# ProProject_PetCareSTM32_MiniSTM32_2024-0.net
KiCad netlist of a schematic drawn in EasyEDA Pro
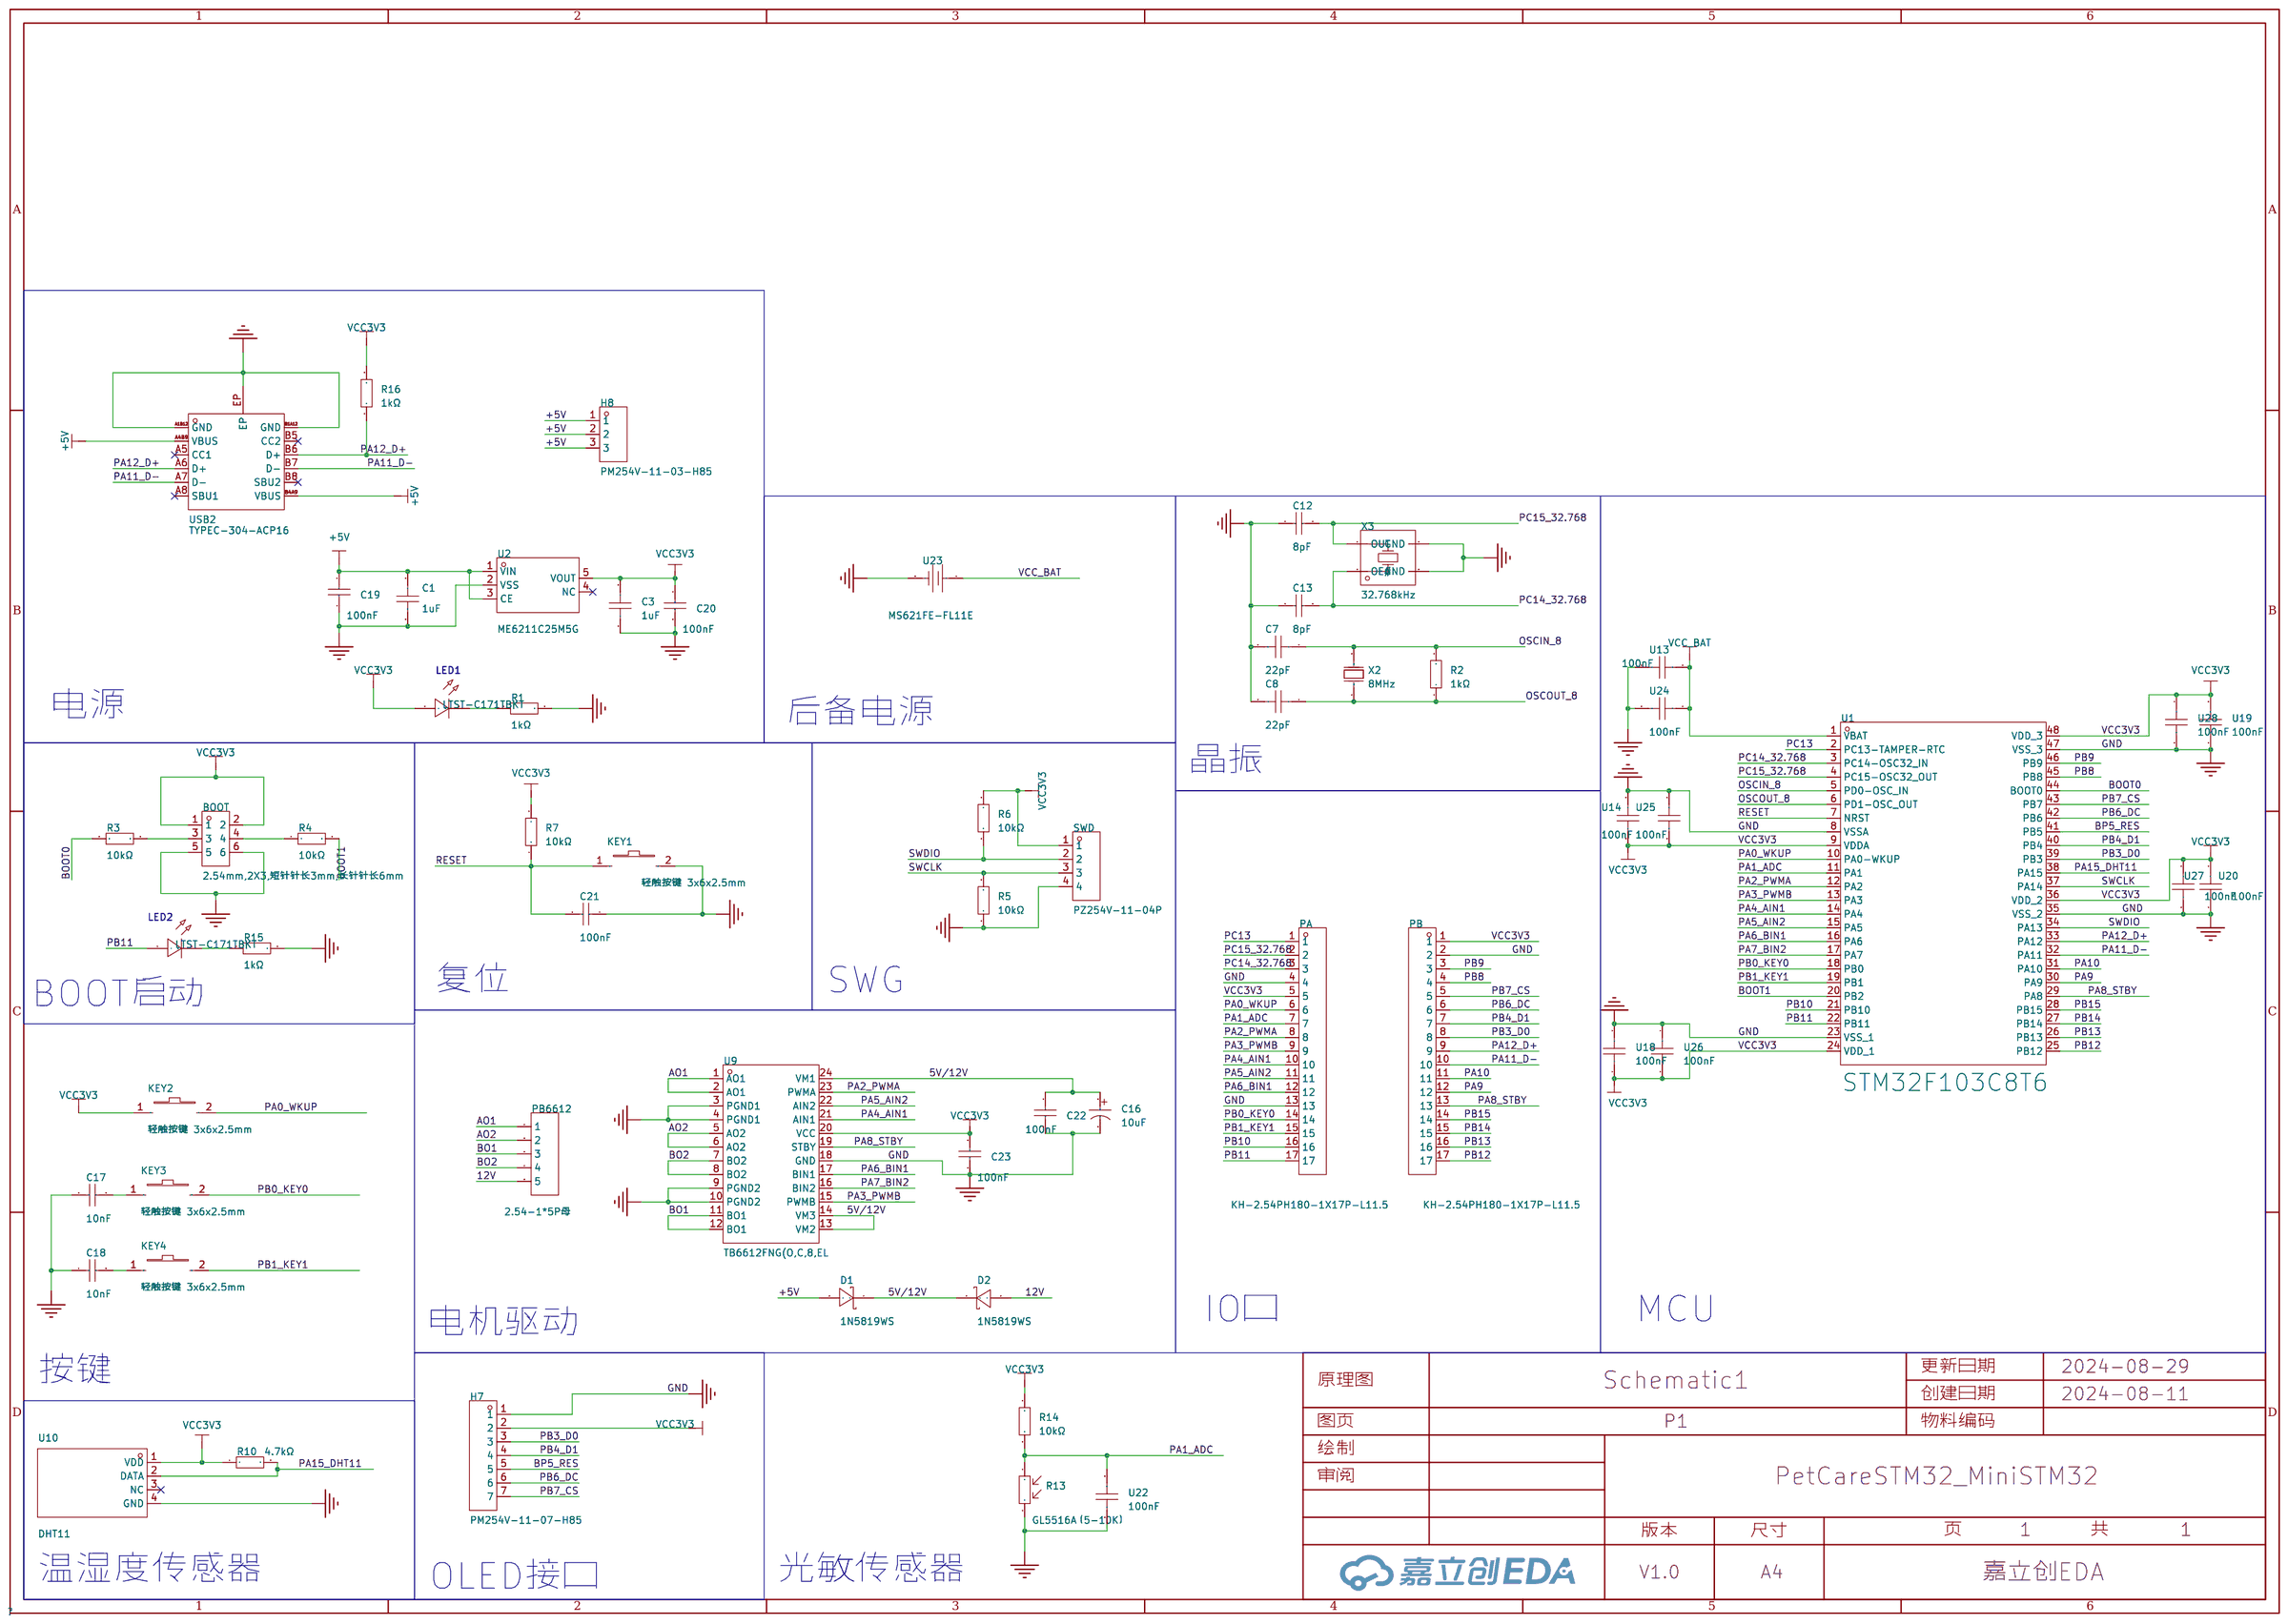
[diagram p0: schematic sheet]

(export (version "E")
  (design (tool "Eeschema 10.0.6"))
  (components
    (comp (ref "BOOT")
      (value "2.54mm,2X3,短针针长3mm,长针针长6mm")
      (footprint "easyedapro:HDR-TH_6P-P2.54-V-M-R2-C3-S2.54-2")
      (libsource (lib "easyedapro") (part "2.54MM,2X3,短针针长3MM,长针针长6MM"))
    )
    (comp (ref "C1")
      (value "1uF")
      (footprint "easyedapro:C0603")
      (description "容值:1uF;精度:±10%;额定电压:50V;材质(温度系数):X5R;")
      (fields
        (field (name "Manufacturer Part") "CL10A105KB8NNNC")
        (field (name "Manufacturer") "SAMSUNG(三星)")
      )
      (libsource (lib "easyedapro") (part "CL10A105KB8NNNC"))
    )
    (comp (ref "C3")
      (value "1uF")
      (footprint "easyedapro:C0603")
      (description "容值:1uF;精度:±10%;额定电压:50V;材质(温度系数):X5R;")
      (fields
        (field (name "Manufacturer Part") "CL10A105KB8NNNC")
        (field (name "Manufacturer") "SAMSUNG(三星)")
      )
      (libsource (lib "easyedapro") (part "CL10A105KB8NNNC"))
    )
    (comp (ref "C7")
      (value "22pF")
      (footprint "easyedapro:C0603")
      (description "容值:22pF;精度:±5%;额定电压:50V;材质(温度系数):C0G;")
      (fields
        (field (name "Manufacturer Part") "CL10C220JB81PNC")
        (field (name "Manufacturer") "SAMSUNG(三星)")
      )
      (libsource (lib "easyedapro") (part "CL10C220JB81PNC"))
    )
    (comp (ref "C8")
      (value "22pF")
      (footprint "easyedapro:C0603")
      (description "容值:22pF;精度:±5%;额定电压:50V;材质(温度系数):C0G;")
      (fields
        (field (name "Manufacturer Part") "CL10C220JB81PNC")
        (field (name "Manufacturer") "SAMSUNG(三星)")
      )
      (libsource (lib "easyedapro") (part "CL10C220JB81PNC"))
    )
    (comp (ref "C12")
      (value "8pF")
      (footprint "easyedapro:C0603")
      (description "容值:8pF;额定电压:50V;材质(温度系数):C0G;")
      (fields (field (name "Manufacturer Part") "0603CG8R0C500NT") (field (name "Manufacturer") "FH(风华)"))
      (libsource (lib "easyedapro") (part "0603CG8R0C500NT_C36508"))
    )
    (comp (ref "C13")
      (value "8pF")
      (footprint "easyedapro:C0603")
      (description "容值:8pF;额定电压:50V;材质(温度系数):C0G;")
      (fields (field (name "Manufacturer Part") "0603CG8R0C500NT") (field (name "Manufacturer") "FH(风华)"))
      (libsource (lib "easyedapro") (part "0603CG8R0C500NT_C36508"))
    )
    (comp (ref "C16")
      (value "10uF")
      (footprint "easyedapro:CAP-TH_BD5.0-P2.00-D0.8-FD")
      (description "容值:10uF;精度:±20%;额定电压:25V;")
      (fields (field (name "Manufacturer Part") "KF100M025C110A") (field (name "Manufacturer") "CapXon(丰宾)"))
      (libsource (lib "easyedapro") (part "KF100M025C110A"))
    )
    (comp (ref "C17")
      (value "10nF")
      (footprint "easyedapro:C0603")
      (description "容值:10nF;精度:±10%;额定电压:50V;材质(温度系数):X7R;")
      (fields
        (field (name "Manufacturer Part") "CC0603KRX7R9BB103")
        (field (name "Manufacturer") "YAGEO(国巨)")
      )
      (libsource (lib "easyedapro") (part "CC0603KRX7R9BB103"))
    )
    (comp (ref "C18")
      (value "10nF")
      (footprint "easyedapro:C0603")
      (description "容值:10nF;精度:±10%;额定电压:50V;材质(温度系数):X7R;")
      (fields
        (field (name "Manufacturer Part") "CC0603KRX7R9BB103")
        (field (name "Manufacturer") "YAGEO(国巨)")
      )
      (libsource (lib "easyedapro") (part "CC0603KRX7R9BB103"))
    )
    (comp (ref "C19")
      (value "100nF")
      (footprint "easyedapro:C0805")
      (description "容值:100nF;精度:±10%;额定电压:50V;材质(温度系数):X7R;")
      (fields
        (field (name "Manufacturer Part") "CL21B104KBCNNNC")
        (field (name "Manufacturer") "SAMSUNG(三星)")
      )
      (libsource (lib "easyedapro") (part "CL21B104KBCNNNC"))
    )
    (comp (ref "C20")
      (value "100nF")
      (footprint "easyedapro:C0805")
      (description "容值:100nF;精度:±10%;额定电压:50V;材质(温度系数):X7R;")
      (fields
        (field (name "Manufacturer Part") "CL21B104KBCNNNC")
        (field (name "Manufacturer") "SAMSUNG(三星)")
      )
      (libsource (lib "easyedapro") (part "CL21B104KBCNNNC"))
    )
    (comp (ref "C21")
      (value "100nF")
      (footprint "easyedapro:C0805")
      (description "容值:100nF;精度:±10%;额定电压:50V;材质(温度系数):X7R;")
      (fields
        (field (name "Manufacturer Part") "CL21B104KBCNNNC")
        (field (name "Manufacturer") "SAMSUNG(三星)")
      )
      (libsource (lib "easyedapro") (part "CL21B104KBCNNNC"))
    )
    (comp (ref "C22")
      (value "100nF")
      (footprint "easyedapro:C0805")
      (description "容值:100nF;精度:±10%;额定电压:50V;材质(温度系数):X7R;")
      (fields
        (field (name "Manufacturer Part") "CL21B104KBCNNNC")
        (field (name "Manufacturer") "SAMSUNG(三星)")
      )
      (libsource (lib "easyedapro") (part "CL21B104KBCNNNC"))
    )
    (comp (ref "C23")
      (value "100nF")
      (footprint "easyedapro:C0805")
      (description "容值:100nF;精度:±10%;额定电压:50V;材质(温度系数):X7R;")
      (fields
        (field (name "Manufacturer Part") "CL21B104KBCNNNC")
        (field (name "Manufacturer") "SAMSUNG(三星)")
      )
      (libsource (lib "easyedapro") (part "CL21B104KBCNNNC"))
    )
    (comp (ref "D1")
      (value "1N5819WS")
      (footprint "easyedapro:SOD-323_L1.8-W1.3-LS2.5-RD")
      (description "正向压降(Vf):600mV@1A;直流反向耐压(Vr):40V;平均整流电流(Io):1A;")
      (fields (field (name "Manufacturer") "Hottech(合科泰)"))
      (libsource (lib "easyedapro") (part "1N5819WS"))
    )
    (comp (ref "D2")
      (value "1N5819WS")
      (footprint "easyedapro:SOD-323_L1.8-W1.3-LS2.5-RD")
      (description "正向压降(Vf):600mV@1A;直流反向耐压(Vr):40V;平均整流电流(Io):1A;")
      (fields (field (name "Manufacturer") "Hottech(合科泰)"))
      (libsource (lib "easyedapro") (part "1N5819WS"))
    )
    (comp (ref "H7")
      (value "PM254V-11-07-H85")
      (footprint "easyedapro:HDR-TH_7P-P2.54-V-F")
      (fields (field (name "Manufacturer") "XFCN(兴飞)"))
      (libsource (lib "easyedapro") (part "PM254V-11-07-H85"))
    )
    (comp (ref "H8")
      (value "PM254V-11-03-H85")
      (footprint "easyedapro:HDR-TH_3P-P2.54-V-F")
      (description "插孔结构:1x3P;间距:2.54mm;行距:-;安装类型:直插;排数:单排;总孔位数:3P;塑高:-;触头材质:黄铜;触头镀层:-;")
      (fields (field (name "Manufacturer") "XFCN(兴飞)"))
      (libsource (lib "easyedapro") (part "PM254V-11-03-H85"))
    )
    (comp (ref "KEY1")
      (value "轻触按键 3x6x2.5mm")
      (footprint "easyedapro:SW-SMD_L6.0-W3.6-LS8.0")
      (libsource (lib "easyedapro") (part "3x6x2.5mm"))
    )
    (comp (ref "KEY2")
      (value "轻触按键 3x6x2.5mm")
      (footprint "easyedapro:SW-SMD_L6.0-W3.6-LS8.0")
      (libsource (lib "easyedapro") (part "3x6x2.5mm"))
    )
    (comp (ref "KEY3")
      (value "轻触按键 3x6x2.5mm")
      (footprint "easyedapro:SW-SMD_L6.0-W3.6-LS8.0")
      (libsource (lib "easyedapro") (part "3x6x2.5mm"))
    )
    (comp (ref "KEY4")
      (value "轻触按键 3x6x2.5mm")
      (footprint "easyedapro:SW-SMD_L6.0-W3.6-LS8.0")
      (libsource (lib "easyedapro") (part "3x6x2.5mm"))
    )
    (comp (ref "LED1")
      (value "LTST-C171TBKT")
      (footprint "easyedapro:LED_0805")
      (fields (field (name "Manufacturer") "LITEON(光宝)"))
      (libsource (lib "easyedapro") (part "LED_B"))
    )
    (comp (ref "LED2")
      (value "LTST-C171TBKT")
      (footprint "easyedapro:LED_0805")
      (fields (field (name "Manufacturer") "LITEON(光宝)"))
      (libsource (lib "easyedapro") (part "LED_B"))
    )
    (comp (ref "PA")
      (value "KH-2.54PH180-1X17P-L11.5")
      (footprint "easyedapro:HDR-TH_17P-P2.54-V-M")
      (fields (field (name "Manufacturer") "kinghelm(金航标)"))
      (libsource (lib "easyedapro") (part "KH-2.54PH180-1X17P-L11.5"))
    )
    (comp (ref "PB")
      (value "KH-2.54PH180-1X17P-L11.5")
      (footprint "easyedapro:HDR-TH_17P-P2.54-V-M")
      (fields (field (name "Manufacturer") "kinghelm(金航标)"))
      (libsource (lib "easyedapro") (part "KH-2.54PH180-1X17P-L11.5"))
    )
    (comp (ref "PB6612")
      (value "2.54-1*5P母")
      (footprint "easyedapro:HDR-TH_5P-P2.54-V-F")
      (description "插孔结构:1x5P;间距:2.54mm;行距:-;安装类型:直插;排数:单排;总孔位数:5P;塑高:-;触头材质:-;触头镀层:-;")
      (fields (field (name "Manufacturer") "BOOMELE(博穆精密)"))
      (libsource (lib "easyedapro") (part "Header-Female-2.54_1x5"))
    )
    (comp (ref "R1")
      (value "1kΩ")
      (footprint "easyedapro:R0603")
      (description "电阻类型:厚膜电阻;阻值:1kΩ;精度:±1%;功率:100mW;最大工作电压:75V;温度系数:±100ppm/°C;")
      (fields (field (name "Manufacturer Part") "RC0603FR-071KL") (field (name "Manufacturer") "YAGEO(国巨)"))
      (libsource (lib "easyedapro") (part "RC0603FR-071KL"))
    )
    (comp (ref "R2")
      (value "1kΩ")
      (footprint "easyedapro:R0603")
      (description "电阻类型:厚膜电阻;阻值:1kΩ;精度:±0.5%;功率:100mW;最大工作电压:75V;温度系数:±100ppm/°C;")
      (fields
        (field (name "Manufacturer Part") "0603WAD1001T5E")
        (field (name "Manufacturer") "UNI-ROYAL(厚声)")
      )
      (libsource (lib "easyedapro") (part "0603WAD1001T5E"))
    )
    (comp (ref "R3")
      (value "10kΩ")
      (footprint "easyedapro:R0603")
      (description "电阻类型:厚膜电阻;阻值:10kΩ;精度:±1%;功率:100mW;最大工作电压:75V;温度系数:±100ppm/°C;")
      (fields
        (field (name "Manufacturer Part") "0603WAF1002T5E")
        (field (name "Manufacturer") "UNI-ROYAL(厚声)")
      )
      (libsource (lib "easyedapro") (part "0603WAF1002T5E"))
    )
    (comp (ref "R4")
      (value "10kΩ")
      (footprint "easyedapro:R0603")
      (description "电阻类型:厚膜电阻;阻值:10kΩ;精度:±1%;功率:100mW;最大工作电压:75V;温度系数:±100ppm/°C;")
      (fields
        (field (name "Manufacturer Part") "0603WAF1002T5E")
        (field (name "Manufacturer") "UNI-ROYAL(厚声)")
      )
      (libsource (lib "easyedapro") (part "0603WAF1002T5E"))
    )
    (comp (ref "R5")
      (value "10kΩ")
      (footprint "easyedapro:R0603")
      (description "电阻类型:厚膜电阻;阻值:10kΩ;精度:±1%;功率:100mW;最大工作电压:75V;温度系数:±100ppm/°C;")
      (fields
        (field (name "Manufacturer Part") "0603WAF1002T5E")
        (field (name "Manufacturer") "UNI-ROYAL(厚声)")
      )
      (libsource (lib "easyedapro") (part "0603WAF1002T5E"))
    )
    (comp (ref "R6")
      (value "10kΩ")
      (footprint "easyedapro:R0603")
      (description "电阻类型:厚膜电阻;阻值:10kΩ;精度:±1%;功率:100mW;最大工作电压:75V;温度系数:±100ppm/°C;")
      (fields
        (field (name "Manufacturer Part") "0603WAF1002T5E")
        (field (name "Manufacturer") "UNI-ROYAL(厚声)")
      )
      (libsource (lib "easyedapro") (part "0603WAF1002T5E"))
    )
    (comp (ref "R7")
      (value "10kΩ")
      (footprint "easyedapro:R0603")
      (description "电阻类型:厚膜电阻;阻值:10kΩ;精度:±1%;功率:100mW;最大工作电压:75V;温度系数:±100ppm/°C;")
      (fields
        (field (name "Manufacturer Part") "0603WAF1002T5E")
        (field (name "Manufacturer") "UNI-ROYAL(厚声)")
      )
      (libsource (lib "easyedapro") (part "0603WAF1002T5E"))
    )
    (comp (ref "R10")
      (value "4.7kΩ")
      (footprint "easyedapro:R1206")
      (description "电阻类型:厚膜电阻;阻值:4.7kΩ;精度:±1%;功率:250mW;最大工作电压:200V;温度系数:±100ppm/°C;")
      (fields
        (field (name "Manufacturer Part") "1206W4F4701T5E")
        (field (name "Manufacturer") "UNI-ROYAL(厚声)")
      )
      (libsource (lib "easyedapro") (part "1206W4F4701T5E"))
    )
    (comp (ref "R13")
      (value "GL5516A（5-10K）")
      (footprint "easyedapro:RES-TH_L5.1-W4.3-P3.40_GL55")
      (description "暗电阻:200kΩ;亮电阻 @ 10Lux:5kΩ~10kΩ;光谱峰值(波长):540nm;")
      (fields (field (name "Manufacturer") "JCHL(晶创和立)"))
      (libsource (lib "easyedapro") (part "GL5516A(5-10K)"))
    )
    (comp (ref "R14")
      (value "10kΩ")
      (footprint "easyedapro:R0603")
      (description "电阻类型:厚膜电阻;阻值:10kΩ;精度:±1%;功率:100mW;最大工作电压:75V;温度系数:±100ppm/°C;")
      (fields
        (field (name "Manufacturer Part") "0603WAF1002T5E")
        (field (name "Manufacturer") "UNI-ROYAL(厚声)")
      )
      (libsource (lib "easyedapro") (part "0603WAF1002T5E"))
    )
    (comp (ref "R15")
      (value "1kΩ")
      (footprint "easyedapro:R0603")
      (description "电阻类型:厚膜电阻;阻值:1kΩ;精度:±1%;功率:100mW;最大工作电压:75V;温度系数:±100ppm/°C;")
      (fields (field (name "Manufacturer Part") "RC0603FR-071KL") (field (name "Manufacturer") "YAGEO(国巨)"))
      (libsource (lib "easyedapro") (part "RC0603FR-071KL"))
    )
    (comp (ref "R16")
      (value "1kΩ")
      (footprint "easyedapro:R0603")
      (description "电阻类型:厚膜电阻;阻值:1kΩ;精度:±0.5%;功率:100mW;最大工作电压:75V;温度系数:±100ppm/°C;")
      (fields
        (field (name "Manufacturer Part") "0603WAD1001T5E")
        (field (name "Manufacturer") "UNI-ROYAL(厚声)")
      )
      (libsource (lib "easyedapro") (part "0603WAD1001T5E"))
    )
    (comp (ref "SWD")
      (value "PZ254V-11-04P")
      (footprint "easyedapro:HDR-TH_4P-P2.54-V-M")
      (fields (field (name "Manufacturer") "XFCN(兴飞)"))
      (libsource (lib "easyedapro") (part "PZ254V-11-04P_C2691448"))
    )
    (comp (ref "U1")
      (value "STM32F103C8T6")
      (footprint "easyedapro:LQFP-48_L7.0-W7.0-P0.50-LS9.0-BL")
      (description "CPU内核:ARM-M3;程序存储容量:64KB;RAM总容量:20KB;GPIO端口数量:37;工作电压范围:2V~3.6V;CPU最大主频:72MHz;程序存储器类型:FLASH;")
      (fields (field (name "Manufacturer") "ST(意法半导体)"))
      (libsource (lib "easyedapro") (part "STM32F103C8T6"))
    )
    (comp (ref "U2")
      (value "ME6211C25M5G")
      (footprint "easyedapro:SOT-23-5_L2.9-W1.7-P0.95-LS2.8-BL")
      (fields (field (name "Manufacturer") "MICRONE(南京微盟)"))
      (libsource (lib "easyedapro") (part "ME6211C25M5G"))
    )
    (comp (ref "U9")
      (value "TB6612FNG(O,C,8,EL")
      (footprint "easyedapro:SSOP-24_L8.4-W5.8-P0.65-LS7.8-BL")
      (description "双直流电机驱动器集成电路")
      (fields (field (name "Manufacturer") "TOSHIBA(东芝)"))
      (libsource (lib "easyedapro") (part "TB6612FNG(O,C,8,EL"))
    )
    (comp (ref "U10")
      (value "DHT11")
      (footprint "easyedapro:SENSOR-TH_DHT11")
      (description "新款电容式数字温湿度传感器,老款已停产16.1x12.6x5.8mm")
      (fields (field (name "Manufacturer") "广州奥松"))
      (libsource (lib "easyedapro") (part "DHT11"))
    )
    (comp (ref "U13")
      (value "100nF")
      (footprint "easyedapro:C0603")
      (description "容值:100nF;精度:±10%;额定电压:50V;材质(温度系数):X7R;")
      (fields
        (field (name "Manufacturer Part") "CGA0603X7R104K500JT")
        (field (name "Manufacturer") "HRE(芯声)")
      )
      (libsource (lib "easyedapro") (part "CGA0603X7R104K500JT"))
    )
    (comp (ref "U14")
      (value "100nF")
      (footprint "easyedapro:C0603")
      (description "容值:100nF;精度:±10%;额定电压:50V;材质(温度系数):X7R;")
      (fields
        (field (name "Manufacturer Part") "CGA0603X7R104K500JT")
        (field (name "Manufacturer") "HRE(芯声)")
      )
      (libsource (lib "easyedapro") (part "CGA0603X7R104K500JT"))
    )
    (comp (ref "U18")
      (value "100nF")
      (footprint "easyedapro:C0603")
      (description "容值:100nF;精度:±10%;额定电压:50V;材质(温度系数):X7R;")
      (fields
        (field (name "Manufacturer Part") "CGA0603X7R104K500JT")
        (field (name "Manufacturer") "HRE(芯声)")
      )
      (libsource (lib "easyedapro") (part "CGA0603X7R104K500JT"))
    )
    (comp (ref "U19")
      (value "100nF")
      (footprint "easyedapro:C0603")
      (description "容值:100nF;精度:±10%;额定电压:50V;材质(温度系数):X7R;")
      (fields
        (field (name "Manufacturer Part") "CGA0603X7R104K500JT")
        (field (name "Manufacturer") "HRE(芯声)")
      )
      (libsource (lib "easyedapro") (part "CGA0603X7R104K500JT"))
    )
    (comp (ref "U20")
      (value "100nF")
      (footprint "easyedapro:C0603")
      (description "容值:100nF;精度:±10%;额定电压:50V;材质(温度系数):X7R;")
      (fields
        (field (name "Manufacturer Part") "CGA0603X7R104K500JT")
        (field (name "Manufacturer") "HRE(芯声)")
      )
      (libsource (lib "easyedapro") (part "CGA0603X7R104K500JT"))
    )
    (comp (ref "U22")
      (value "100nF")
      (footprint "easyedapro:C0603")
      (description "容值:100nF;精度:±10%;额定电压:50V;材质(温度系数):X7R;")
      (fields
        (field (name "Manufacturer Part") "CGA0603X7R104K500JT")
        (field (name "Manufacturer") "HRE(芯声)")
      )
      (libsource (lib "easyedapro") (part "CGA0603X7R104K500JT"))
    )
    (comp (ref "U23")
      (value "MS621FE-FL11E")
      (footprint "easyedapro:BAT-SMD_FL11E")
      (description "FL11E 3.3V可充电纽扣电池 5.5mAH")
      (fields (field (name "Manufacturer") "Seiko(精工)"))
      (libsource (lib "easyedapro") (part "MS621FE-FL11E"))
    )
    (comp (ref "U24")
      (value "100nF")
      (footprint "easyedapro:C0603")
      (description "容值:100nF;精度:±10%;额定电压:50V;材质(温度系数):X7R;")
      (fields
        (field (name "Manufacturer Part") "CGA0603X7R104K500JT")
        (field (name "Manufacturer") "HRE(芯声)")
      )
      (libsource (lib "easyedapro") (part "CGA0603X7R104K500JT"))
    )
    (comp (ref "U25")
      (value "100nF")
      (footprint "easyedapro:C0603")
      (description "容值:100nF;精度:±10%;额定电压:50V;材质(温度系数):X7R;")
      (fields
        (field (name "Manufacturer Part") "CGA0603X7R104K500JT")
        (field (name "Manufacturer") "HRE(芯声)")
      )
      (libsource (lib "easyedapro") (part "CGA0603X7R104K500JT"))
    )
    (comp (ref "U26")
      (value "100nF")
      (footprint "easyedapro:C0603")
      (description "容值:100nF;精度:±10%;额定电压:50V;材质(温度系数):X7R;")
      (fields
        (field (name "Manufacturer Part") "CGA0603X7R104K500JT")
        (field (name "Manufacturer") "HRE(芯声)")
      )
      (libsource (lib "easyedapro") (part "CGA0603X7R104K500JT"))
    )
    (comp (ref "U27")
      (value "100nF")
      (footprint "easyedapro:C0603")
      (description "容值:100nF;精度:±10%;额定电压:50V;材质(温度系数):X7R;")
      (fields
        (field (name "Manufacturer Part") "CGA0603X7R104K500JT")
        (field (name "Manufacturer") "HRE(芯声)")
      )
      (libsource (lib "easyedapro") (part "CGA0603X7R104K500JT"))
    )
    (comp (ref "U28")
      (value "100nF")
      (footprint "easyedapro:C0603")
      (description "容值:100nF;精度:±10%;额定电压:50V;材质(温度系数):X7R;")
      (fields
        (field (name "Manufacturer Part") "CGA0603X7R104K500JT")
        (field (name "Manufacturer") "HRE(芯声)")
      )
      (libsource (lib "easyedapro") (part "CGA0603X7R104K500JT"))
    )
    (comp (ref "USB2")
      (value "TYPEC-304-ACP16")
      (footprint "easyedapro:USB-C-SMD_TYPE-C-16P-1")
      (fields (field (name "Manufacturer") "XUNPU(讯普)"))
      (libsource (lib "easyedapro") (part "TYPEC-304-ACP16"))
    )
    (comp (ref "X2")
      (value "8MHz")
      (footprint "easyedapro:OSC-SMD_L5.0-W3.2")
      (description "晶振类型:贴片晶振;频率:8MHz;常温频差:±20ppm;外接负载电容:18pF;频率稳定度(全温):±30ppm;")
      (fields
        (field (name "Manufacturer Part") "ABM3-8.000MHZ-D2Y-T")
        (field (name "Manufacturer") "ABRACON")
      )
      (libsource (lib "easyedapro") (part "ABM3-8.000MHZ-D2Y-T"))
    )
    (comp (ref "X3")
      (value "32.768kHz")
      (footprint "easyedapro:CRYSTAL-SMD_4P-L8.0-W3.8-BL")
      (description "晶振类型:-;频率:32.768kHz;常温频差:±20ppm;外接负载电容:12.5pF;频率稳定度(全温):-;")
      (fields (field (name "Manufacturer Part") "ABS25-32.768KHZ-T") (field (name "Manufacturer") "ABRACON"))
      (libsource (lib "easyedapro") (part "ABS25-32.768KHZ-T"))
    )
  )
  (nets
    (net (code "1") (name "+5V") (class "Default")
      (node (ref "C1") (pin "2") (pinfunction "2_2") (pintype "unspecified"))
      (node (ref "C19") (pin "2") (pinfunction "2_2") (pintype "input"))
      (node (ref "D1") (pin "2") (pinfunction "A_2") (pintype "unspecified"))
      (node (ref "H8") (pin "1") (pinfunction "1_1") (pintype "unspecified"))
      (node (ref "H8") (pin "2") (pinfunction "2_2") (pintype "unspecified"))
      (node (ref "H8") (pin "3") (pinfunction "3_3") (pintype "unspecified"))
      (node (ref "U2") (pin "1") (pinfunction "VIN_1") (pintype "unspecified"))
      (node (ref "U2") (pin "3") (pinfunction "CE_3") (pintype "unspecified"))
      (node (ref "USB2") (pin "A4B9") (pinfunction "VBUS_A4B9") (pintype "unspecified"))
      (node (ref "USB2") (pin "B4A9") (pinfunction "VBUS_B4A9") (pintype "unspecified"))
    )
    (net (code "2") (name "/5V{slash}12V") (class "Default")
      (node (ref "C16") (pin "1") (pinfunction "1_1") (pintype "input"))
      (node (ref "C22") (pin "2") (pinfunction "2_2") (pintype "input"))
      (node (ref "D1") (pin "1") (pinfunction "K_1") (pintype "unspecified"))
      (node (ref "D2") (pin "1") (pinfunction "K_1") (pintype "unspecified"))
      (node (ref "U9") (pin "13") (pinfunction "VM2_13") (pintype "unspecified"))
      (node (ref "U9") (pin "14") (pinfunction "VM3_14") (pintype "unspecified"))
      (node (ref "U9") (pin "24") (pinfunction "VM1_24") (pintype "unspecified"))
    )
    (net (code "3") (name "/12V") (class "Default")
      (node (ref "D2") (pin "2") (pinfunction "A_2") (pintype "unspecified"))
      (node (ref "PB6612") (pin "5") (pinfunction "5_5") (pintype "input"))
    )
    (net (code "4") (name "/AO1") (class "Default")
      (node (ref "PB6612") (pin "1") (pinfunction "1_1") (pintype "input"))
      (node (ref "U9") (pin "1") (pinfunction "AO1_1") (pintype "unspecified"))
      (node (ref "U9") (pin "2") (pinfunction "AO1_2") (pintype "unspecified"))
    )
    (net (code "5") (name "/AO2") (class "Default")
      (node (ref "PB6612") (pin "2") (pinfunction "2_2") (pintype "input"))
      (node (ref "U9") (pin "5") (pinfunction "AO2_5") (pintype "unspecified"))
      (node (ref "U9") (pin "6") (pinfunction "AO2_6") (pintype "unspecified"))
    )
    (net (code "6") (name "/BO1") (class "Default")
      (node (ref "PB6612") (pin "3") (pinfunction "3_3") (pintype "input"))
      (node (ref "U9") (pin "11") (pinfunction "BO1_11") (pintype "unspecified"))
      (node (ref "U9") (pin "12") (pinfunction "BO1_12") (pintype "unspecified"))
    )
    (net (code "7") (name "/BO2") (class "Default")
      (node (ref "PB6612") (pin "4") (pinfunction "4_4") (pintype "input"))
      (node (ref "U9") (pin "7") (pinfunction "BO2_7") (pintype "unspecified"))
      (node (ref "U9") (pin "8") (pinfunction "BO2_8") (pintype "unspecified"))
    )
    (net (code "8") (name "/BOOT0") (class "Default")
      (node (ref "R3") (pin "1") (pinfunction "1_1") (pintype "input"))
      (node (ref "U1") (pin "44") (pinfunction "BOOT0_44") (pintype "unspecified"))
    )
    (net (code "9") (name "/BOOT1") (class "Default")
      (node (ref "R4") (pin "2") (pinfunction "2_2") (pintype "input"))
      (node (ref "U1") (pin "20") (pinfunction "PB2_20") (pintype "unspecified"))
    )
    (net (code "10") (name "/BP5_RES") (class "Default")
      (node (ref "H7") (pin "5") (pinfunction "5_5") (pintype "unspecified"))
      (node (ref "U1") (pin "41") (pinfunction "PB5_41") (pintype "unspecified"))
    )
    (net (code "11") (name "/OSCIN_8") (class "Default")
      (node (ref "C7") (pin "1") (pinfunction "1_1") (pintype "unspecified"))
      (node (ref "R2") (pin "2") (pinfunction "2_2") (pintype "input"))
      (node (ref "U1") (pin "5") (pinfunction "PD0-OSC_IN_5") (pintype "unspecified"))
      (node (ref "X2") (pin "2") (pinfunction "OSC2_2") (pintype "input"))
    )
    (net (code "12") (name "/OSCOUT_8") (class "Default")
      (node (ref "C8") (pin "1") (pinfunction "1_1") (pintype "unspecified"))
      (node (ref "R2") (pin "1") (pinfunction "1_1") (pintype "input"))
      (node (ref "U1") (pin "6") (pinfunction "PD1-OSC_OUT_6") (pintype "unspecified"))
      (node (ref "X2") (pin "1") (pinfunction "OSC1_1") (pintype "input"))
    )
    (net (code "13") (name "/PA0_WKUP") (class "Default")
      (node (ref "KEY2") (pin "2") (pinfunction "2_2") (pintype "input"))
      (node (ref "PA") (pin "6") (pinfunction "6_6") (pintype "unspecified"))
      (node (ref "U1") (pin "10") (pinfunction "PA0-WKUP_10") (pintype "unspecified"))
    )
    (net (code "14") (name "/PA1_ADC") (class "Default")
      (node (ref "PA") (pin "7") (pinfunction "7_7") (pintype "unspecified"))
      (node (ref "R13") (pin "1") (pinfunction "1_1") (pintype "input"))
      (node (ref "R14") (pin "1") (pinfunction "1_1") (pintype "input"))
      (node (ref "U1") (pin "11") (pinfunction "PA1_11") (pintype "unspecified"))
      (node (ref "U22") (pin "2") (pinfunction "2_2") (pintype "unspecified"))
    )
    (net (code "15") (name "/PA2_PWMA") (class "Default")
      (node (ref "PA") (pin "8") (pinfunction "8_8") (pintype "unspecified"))
      (node (ref "U1") (pin "12") (pinfunction "PA2_12") (pintype "unspecified"))
      (node (ref "U9") (pin "23") (pinfunction "PWMA_23") (pintype "unspecified"))
    )
    (net (code "16") (name "/PA3_PWMB") (class "Default")
      (node (ref "PA") (pin "9") (pinfunction "9_9") (pintype "unspecified"))
      (node (ref "U1") (pin "13") (pinfunction "PA3_13") (pintype "unspecified"))
      (node (ref "U9") (pin "15") (pinfunction "PWMB_15") (pintype "unspecified"))
    )
    (net (code "17") (name "/PA4_AIN1") (class "Default")
      (node (ref "PA") (pin "10") (pinfunction "10_10") (pintype "unspecified"))
      (node (ref "U1") (pin "14") (pinfunction "PA4_14") (pintype "unspecified"))
      (node (ref "U9") (pin "21") (pinfunction "AIN1_21") (pintype "unspecified"))
    )
    (net (code "18") (name "/PA5_AIN2") (class "Default")
      (node (ref "PA") (pin "11") (pinfunction "11_11") (pintype "unspecified"))
      (node (ref "U1") (pin "15") (pinfunction "PA5_15") (pintype "unspecified"))
      (node (ref "U9") (pin "22") (pinfunction "AIN2_22") (pintype "unspecified"))
    )
    (net (code "19") (name "/PA6_BIN1") (class "Default")
      (node (ref "PA") (pin "12") (pinfunction "12_12") (pintype "unspecified"))
      (node (ref "U1") (pin "16") (pinfunction "PA6_16") (pintype "unspecified"))
      (node (ref "U9") (pin "17") (pinfunction "BIN1_17") (pintype "unspecified"))
    )
    (net (code "20") (name "/PA7_BIN2") (class "Default")
      (node (ref "U1") (pin "17") (pinfunction "PA7_17") (pintype "unspecified"))
      (node (ref "U9") (pin "16") (pinfunction "BIN2_16") (pintype "unspecified"))
    )
    (net (code "21") (name "/PA8_STBY") (class "Default")
      (node (ref "PB") (pin "13") (pinfunction "13_13") (pintype "unspecified"))
      (node (ref "U1") (pin "29") (pinfunction "PA8_29") (pintype "unspecified"))
      (node (ref "U9") (pin "19") (pinfunction "STBY_19") (pintype "unspecified"))
    )
    (net (code "22") (name "/PA9") (class "Default")
      (node (ref "PB") (pin "12") (pinfunction "12_12") (pintype "unspecified"))
      (node (ref "U1") (pin "30") (pinfunction "PA9_30") (pintype "unspecified"))
    )
    (net (code "23") (name "/PA10") (class "Default")
      (node (ref "PB") (pin "11") (pinfunction "11_11") (pintype "unspecified"))
      (node (ref "U1") (pin "31") (pinfunction "PA10_31") (pintype "unspecified"))
    )
    (net (code "24") (name "/PA11_D-") (class "Default")
      (node (ref "PB") (pin "10") (pinfunction "10_10") (pintype "unspecified"))
      (node (ref "U1") (pin "32") (pinfunction "PA11_32") (pintype "unspecified"))
      (node (ref "USB2") (pin "A7") (pinfunction "D-_A7") (pintype "unspecified"))
      (node (ref "USB2") (pin "B7") (pinfunction "D-_B7") (pintype "unspecified"))
    )
    (net (code "25") (name "/PA12_D+") (class "Default")
      (node (ref "PB") (pin "9") (pinfunction "9_9") (pintype "unspecified"))
      (node (ref "R16") (pin "1") (pinfunction "1_1") (pintype "input"))
      (node (ref "U1") (pin "33") (pinfunction "PA12_33") (pintype "unspecified"))
      (node (ref "USB2") (pin "A6") (pinfunction "D+_A6") (pintype "unspecified"))
      (node (ref "USB2") (pin "B6") (pinfunction "D+_B6") (pintype "unspecified"))
    )
    (net (code "26") (name "/PA15_DHT11") (class "Default")
      (node (ref "R10") (pin "2") (pinfunction "2_2") (pintype "input"))
      (node (ref "U1") (pin "38") (pinfunction "PA15_38") (pintype "unspecified"))
      (node (ref "U10") (pin "2") (pinfunction "DATA_2") (pintype "unspecified"))
    )
    (net (code "27") (name "/PB0_KEY0") (class "Default")
      (node (ref "KEY3") (pin "2") (pinfunction "2_2") (pintype "input"))
      (node (ref "PA") (pin "14") (pinfunction "14_14") (pintype "unspecified"))
      (node (ref "U1") (pin "18") (pinfunction "PB0_18") (pintype "unspecified"))
    )
    (net (code "28") (name "/PB1_KEY1") (class "Default")
      (node (ref "KEY4") (pin "2") (pinfunction "2_2") (pintype "input"))
      (node (ref "PA") (pin "15") (pinfunction "15_15") (pintype "unspecified"))
      (node (ref "U1") (pin "19") (pinfunction "PB1_19") (pintype "unspecified"))
    )
    (net (code "29") (name "/PB3_D0") (class "Default")
      (node (ref "H7") (pin "3") (pinfunction "3_3") (pintype "unspecified"))
      (node (ref "PB") (pin "8") (pinfunction "8_8") (pintype "unspecified"))
      (node (ref "U1") (pin "39") (pinfunction "PB3_39") (pintype "unspecified"))
    )
    (net (code "30") (name "/PB4_D1") (class "Default")
      (node (ref "H7") (pin "4") (pinfunction "4_4") (pintype "unspecified"))
      (node (ref "PB") (pin "7") (pinfunction "7_7") (pintype "unspecified"))
      (node (ref "U1") (pin "40") (pinfunction "PB4_40") (pintype "unspecified"))
    )
    (net (code "31") (name "/PB6_DC") (class "Default")
      (node (ref "H7") (pin "6") (pinfunction "6_6") (pintype "unspecified"))
      (node (ref "PB") (pin "6") (pinfunction "6_6") (pintype "unspecified"))
      (node (ref "U1") (pin "42") (pinfunction "PB6_42") (pintype "unspecified"))
    )
    (net (code "32") (name "/PB7_CS") (class "Default")
      (node (ref "H7") (pin "7") (pinfunction "7_7") (pintype "unspecified"))
      (node (ref "PB") (pin "5") (pinfunction "5_5") (pintype "unspecified"))
      (node (ref "U1") (pin "43") (pinfunction "PB7_43") (pintype "unspecified"))
    )
    (net (code "33") (name "/PB8") (class "Default")
      (node (ref "PB") (pin "4") (pinfunction "4_4") (pintype "unspecified"))
      (node (ref "U1") (pin "45") (pinfunction "PB8_45") (pintype "unspecified"))
    )
    (net (code "34") (name "/PB9") (class "Default")
      (node (ref "PB") (pin "3") (pinfunction "3_3") (pintype "unspecified"))
      (node (ref "U1") (pin "46") (pinfunction "PB9_46") (pintype "unspecified"))
    )
    (net (code "35") (name "/PB10") (class "Default")
      (node (ref "PA") (pin "16") (pinfunction "16_16") (pintype "unspecified"))
      (node (ref "U1") (pin "21") (pinfunction "PB10_21") (pintype "unspecified"))
    )
    (net (code "36") (name "/PB11") (class "Default")
      (node (ref "LED2") (pin "2") (pinfunction "A_2") (pintype "input"))
      (node (ref "PA") (pin "17") (pinfunction "17_17") (pintype "unspecified"))
      (node (ref "U1") (pin "22") (pinfunction "PB11_22") (pintype "unspecified"))
    )
    (net (code "37") (name "/PB12") (class "Default")
      (node (ref "PB") (pin "17") (pinfunction "17_17") (pintype "unspecified"))
      (node (ref "U1") (pin "25") (pinfunction "PB12_25") (pintype "unspecified"))
    )
    (net (code "38") (name "/PB13") (class "Default")
      (node (ref "PB") (pin "16") (pinfunction "16_16") (pintype "unspecified"))
      (node (ref "U1") (pin "26") (pinfunction "PB13_26") (pintype "unspecified"))
    )
    (net (code "39") (name "/PB14") (class "Default")
      (node (ref "PB") (pin "15") (pinfunction "15_15") (pintype "unspecified"))
      (node (ref "U1") (pin "27") (pinfunction "PB14_27") (pintype "unspecified"))
    )
    (net (code "40") (name "/PB15") (class "Default")
      (node (ref "PB") (pin "14") (pinfunction "14_14") (pintype "unspecified"))
      (node (ref "U1") (pin "28") (pinfunction "PB15_28") (pintype "unspecified"))
    )
    (net (code "41") (name "/PC13") (class "Default")
      (node (ref "PA") (pin "1") (pinfunction "1_1") (pintype "unspecified"))
      (node (ref "U1") (pin "2") (pinfunction "PC13-TAMPER-RTC_2") (pintype "unspecified"))
    )
    (net (code "42") (name "/PC14_32.768") (class "Default")
      (node (ref "C13") (pin "2") (pinfunction "2_2") (pintype "input"))
      (node (ref "PA") (pin "3") (pinfunction "3_3") (pintype "unspecified"))
      (node (ref "U1") (pin "3") (pinfunction "PC14-OSC32_IN_3") (pintype "unspecified"))
      (node (ref "X3") (pin "1") (pinfunction "OE#_1") (pintype "input"))
    )
    (net (code "43") (name "/PC15_32.768") (class "Default")
      (node (ref "C12") (pin "2") (pinfunction "2_2") (pintype "input"))
      (node (ref "PA") (pin "2") (pinfunction "2_2") (pintype "unspecified"))
      (node (ref "U1") (pin "4") (pinfunction "PC15-OSC32_OUT_4") (pintype "unspecified"))
      (node (ref "X3") (pin "4") (pinfunction "OUT_4") (pintype "input"))
    )
    (net (code "44") (name "/RESET") (class "Default")
      (node (ref "C21") (pin "2") (pinfunction "2_2") (pintype "input"))
      (node (ref "KEY1") (pin "1") (pinfunction "1_1") (pintype "input"))
      (node (ref "R7") (pin "1") (pinfunction "1_1") (pintype "input"))
      (node (ref "U1") (pin "7") (pinfunction "NRST_7") (pintype "unspecified"))
    )
    (net (code "45") (name "/SWCLK") (class "Default")
      (node (ref "R5") (pin "2") (pinfunction "2_2") (pintype "input"))
      (node (ref "SWD") (pin "3") (pinfunction "3_3") (pintype "unspecified"))
      (node (ref "U1") (pin "37") (pinfunction "PA14_37") (pintype "unspecified"))
    )
    (net (code "46") (name "/SWDIO") (class "Default")
      (node (ref "R6") (pin "1") (pinfunction "1_1") (pintype "input"))
      (node (ref "SWD") (pin "2") (pinfunction "2_2") (pintype "unspecified"))
      (node (ref "U1") (pin "34") (pinfunction "PA13_34") (pintype "unspecified"))
    )
    (net (code "47") (name "GND") (class "Default")
      (node (ref "BOOT") (pin "5") (pinfunction "5_5") (pintype "unspecified"))
      (node (ref "BOOT") (pin "6") (pinfunction "6_6") (pintype "unspecified"))
      (node (ref "C1") (pin "1") (pinfunction "1_1") (pintype "unspecified"))
      (node (ref "C12") (pin "1") (pinfunction "1_1") (pintype "input"))
      (node (ref "C13") (pin "1") (pinfunction "1_1") (pintype "input"))
      (node (ref "C16") (pin "2") (pinfunction "2_2") (pintype "input"))
      (node (ref "C17") (pin "2") (pinfunction "2_2") (pintype "input"))
      (node (ref "C18") (pin "1") (pinfunction "1_1") (pintype "input"))
      (node (ref "C19") (pin "1") (pinfunction "1_1") (pintype "input"))
      (node (ref "C20") (pin "1") (pinfunction "1_1") (pintype "input"))
      (node (ref "C21") (pin "1") (pinfunction "1_1") (pintype "input"))
      (node (ref "C22") (pin "1") (pinfunction "1_1") (pintype "input"))
      (node (ref "C23") (pin "1") (pinfunction "1_1") (pintype "input"))
      (node (ref "C3") (pin "1") (pinfunction "1_1") (pintype "unspecified"))
      (node (ref "C7") (pin "2") (pinfunction "2_2") (pintype "unspecified"))
      (node (ref "C8") (pin "2") (pinfunction "2_2") (pintype "unspecified"))
      (node (ref "H7") (pin "1") (pinfunction "1_1") (pintype "unspecified"))
      (node (ref "KEY1") (pin "2") (pinfunction "2_2") (pintype "input"))
      (node (ref "PA") (pin "13") (pinfunction "13_13") (pintype "unspecified"))
      (node (ref "PA") (pin "4") (pinfunction "4_4") (pintype "unspecified"))
      (node (ref "PB") (pin "2") (pinfunction "2_2") (pintype "unspecified"))
      (node (ref "R1") (pin "2") (pinfunction "2_2") (pintype "input"))
      (node (ref "R13") (pin "2") (pinfunction "2_2") (pintype "input"))
      (node (ref "R15") (pin "2") (pinfunction "2_2") (pintype "input"))
      (node (ref "R5") (pin "1") (pinfunction "1_1") (pintype "input"))
      (node (ref "SWD") (pin "4") (pinfunction "4_4") (pintype "unspecified"))
      (node (ref "U1") (pin "23") (pinfunction "VSS_1_23") (pintype "unspecified"))
      (node (ref "U1") (pin "35") (pinfunction "VSS_2_35") (pintype "unspecified"))
      (node (ref "U1") (pin "47") (pinfunction "VSS_3_47") (pintype "unspecified"))
      (node (ref "U1") (pin "8") (pinfunction "VSSA_8") (pintype "unspecified"))
      (node (ref "U10") (pin "4") (pinfunction "GND_4") (pintype "unspecified"))
      (node (ref "U13") (pin "2") (pinfunction "2_2") (pintype "unspecified"))
      (node (ref "U14") (pin "2") (pinfunction "2_2") (pintype "unspecified"))
      (node (ref "U18") (pin "2") (pinfunction "2_2") (pintype "unspecified"))
      (node (ref "U19") (pin "1") (pinfunction "1_1") (pintype "unspecified"))
      (node (ref "U2") (pin "2") (pinfunction "VSS_2") (pintype "unspecified"))
      (node (ref "U20") (pin "1") (pinfunction "1_1") (pintype "unspecified"))
      (node (ref "U22") (pin "1") (pinfunction "1_1") (pintype "unspecified"))
      (node (ref "U23") (pin "2") (pinfunction "-_2") (pintype "unspecified"))
      (node (ref "U24") (pin "2") (pinfunction "2_2") (pintype "unspecified"))
      (node (ref "U25") (pin "1") (pinfunction "1_1") (pintype "unspecified"))
      (node (ref "U26") (pin "1") (pinfunction "1_1") (pintype "unspecified"))
      (node (ref "U27") (pin "2") (pinfunction "2_2") (pintype "unspecified"))
      (node (ref "U28") (pin "2") (pinfunction "2_2") (pintype "unspecified"))
      (node (ref "U9") (pin "10") (pinfunction "PGND2_10") (pintype "unspecified"))
      (node (ref "U9") (pin "18") (pinfunction "GND_18") (pintype "unspecified"))
      (node (ref "U9") (pin "3") (pinfunction "PGND1_3") (pintype "unspecified"))
      (node (ref "U9") (pin "4") (pinfunction "PGND1_4") (pintype "unspecified"))
      (node (ref "U9") (pin "9") (pinfunction "PGND2_9") (pintype "unspecified"))
      (node (ref "USB2") (pin "A1B12") (pinfunction "GND_A1B12") (pintype "unspecified"))
      (node (ref "USB2") (pin "B1A12") (pinfunction "GND_B1A12") (pintype "unspecified"))
      (node (ref "USB2") (pin "EP") (pinfunction "EP_EP") (pintype "unspecified"))
      (node (ref "X3") (pin "2") (pinfunction "GND_2") (pintype "input"))
      (node (ref "X3") (pin "3") (pinfunction "GND_3") (pintype "input"))
    )
    (net (code "48") (name "Net-(BOOT-Pad3)") (class "Default")
      (node (ref "BOOT") (pin "3") (pinfunction "3_3") (pintype "unspecified"))
      (node (ref "R3") (pin "2") (pinfunction "2_2") (pintype "input"))
    )
    (net (code "49") (name "Net-(BOOT-Pad4)") (class "Default")
      (node (ref "BOOT") (pin "4") (pinfunction "4_4") (pintype "unspecified"))
      (node (ref "R4") (pin "1") (pinfunction "1_1") (pintype "input"))
    )
    (net (code "50") (name "Net-(C17-Pad1)") (class "Default")
      (node (ref "C17") (pin "1") (pinfunction "1_1") (pintype "input"))
      (node (ref "KEY3") (pin "1") (pinfunction "1_1") (pintype "input"))
    )
    (net (code "51") (name "Net-(C18-Pad2)") (class "Default")
      (node (ref "C18") (pin "2") (pinfunction "2_2") (pintype "input"))
      (node (ref "KEY4") (pin "1") (pinfunction "1_1") (pintype "input"))
    )
    (net (code "52") (name "Net-(LED1-C)") (class "Default")
      (node (ref "LED1") (pin "1") (pinfunction "C_1") (pintype "input"))
      (node (ref "R1") (pin "1") (pinfunction "1_1") (pintype "input"))
    )
    (net (code "53") (name "Net-(LED2-C)") (class "Default")
      (node (ref "LED2") (pin "1") (pinfunction "C_1") (pintype "input"))
      (node (ref "R15") (pin "1") (pinfunction "1_1") (pintype "input"))
    )
    (net (code "54") (name "VCC3V3") (class "Default")
      (node (ref "BOOT") (pin "1") (pinfunction "1_1") (pintype "unspecified"))
      (node (ref "BOOT") (pin "2") (pinfunction "2_2") (pintype "unspecified"))
      (node (ref "C20") (pin "2") (pinfunction "2_2") (pintype "input"))
      (node (ref "C23") (pin "2") (pinfunction "2_2") (pintype "input"))
      (node (ref "C3") (pin "2") (pinfunction "2_2") (pintype "unspecified"))
      (node (ref "H7") (pin "2") (pinfunction "2_2") (pintype "unspecified"))
      (node (ref "KEY2") (pin "1") (pinfunction "1_1") (pintype "input"))
      (node (ref "LED1") (pin "2") (pinfunction "A_2") (pintype "input"))
      (node (ref "PA") (pin "5") (pinfunction "5_5") (pintype "unspecified"))
      (node (ref "PB") (pin "1") (pinfunction "1_1") (pintype "unspecified"))
      (node (ref "R10") (pin "1") (pinfunction "1_1") (pintype "input"))
      (node (ref "R14") (pin "2") (pinfunction "2_2") (pintype "input"))
      (node (ref "R16") (pin "2") (pinfunction "2_2") (pintype "input"))
      (node (ref "R6") (pin "2") (pinfunction "2_2") (pintype "input"))
      (node (ref "R7") (pin "2") (pinfunction "2_2") (pintype "input"))
      (node (ref "SWD") (pin "1") (pinfunction "1_1") (pintype "unspecified"))
      (node (ref "U1") (pin "24") (pinfunction "VDD_1_24") (pintype "unspecified"))
      (node (ref "U1") (pin "36") (pinfunction "VDD_2_36") (pintype "unspecified"))
      (node (ref "U1") (pin "48") (pinfunction "VDD_3_48") (pintype "unspecified"))
      (node (ref "U1") (pin "9") (pinfunction "VDDA_9") (pintype "unspecified"))
      (node (ref "U10") (pin "1") (pinfunction "VDD_1") (pintype "unspecified"))
      (node (ref "U14") (pin "1") (pinfunction "1_1") (pintype "unspecified"))
      (node (ref "U18") (pin "1") (pinfunction "1_1") (pintype "unspecified"))
      (node (ref "U19") (pin "2") (pinfunction "2_2") (pintype "unspecified"))
      (node (ref "U2") (pin "5") (pinfunction "VOUT_5") (pintype "unspecified"))
      (node (ref "U20") (pin "2") (pinfunction "2_2") (pintype "unspecified"))
      (node (ref "U25") (pin "2") (pinfunction "2_2") (pintype "unspecified"))
      (node (ref "U26") (pin "2") (pinfunction "2_2") (pintype "unspecified"))
      (node (ref "U27") (pin "1") (pinfunction "1_1") (pintype "unspecified"))
      (node (ref "U28") (pin "1") (pinfunction "1_1") (pintype "unspecified"))
      (node (ref "U9") (pin "20") (pinfunction "VCC_20") (pintype "unspecified"))
    )
    (net (code "55") (name "VCC_BAT") (class "Default")
      (node (ref "U1") (pin "1") (pinfunction "VBAT_1") (pintype "unspecified"))
      (node (ref "U13") (pin "1") (pinfunction "1_1") (pintype "unspecified"))
      (node (ref "U23") (pin "1") (pinfunction "+_1") (pintype "unspecified"))
      (node (ref "U24") (pin "1") (pinfunction "1_1") (pintype "unspecified"))
    )
    (net (code "56") (name "unconnected-(U2-NC-Pad4)") (class "Default")
      (node (ref "U2") (pin "4") (pinfunction "NC_4") (pintype "unspecified+no_connect"))
    )
    (net (code "57") (name "unconnected-(U10-NC-Pad3)") (class "Default")
      (node (ref "U10") (pin "3") (pinfunction "NC_3") (pintype "unspecified+no_connect"))
    )
    (net (code "58") (name "unconnected-(USB2-CC1-PadA5)") (class "Default")
      (node (ref "USB2") (pin "A5") (pinfunction "CC1_A5") (pintype "unspecified+no_connect"))
    )
    (net (code "59") (name "unconnected-(USB2-CC2-PadB5)") (class "Default")
      (node (ref "USB2") (pin "B5") (pinfunction "CC2_B5") (pintype "unspecified+no_connect"))
    )
    (net (code "60") (name "unconnected-(USB2-SBU1-PadA8)") (class "Default")
      (node (ref "USB2") (pin "A8") (pinfunction "SBU1_A8") (pintype "unspecified+no_connect"))
    )
    (net (code "61") (name "unconnected-(USB2-SBU2-PadB8)") (class "Default")
      (node (ref "USB2") (pin "B8") (pinfunction "SBU2_B8") (pintype "unspecified+no_connect"))
    )
  )
)
